# converter_schematic.net
KiCad netlist of a schematic drawn in Altium Designer
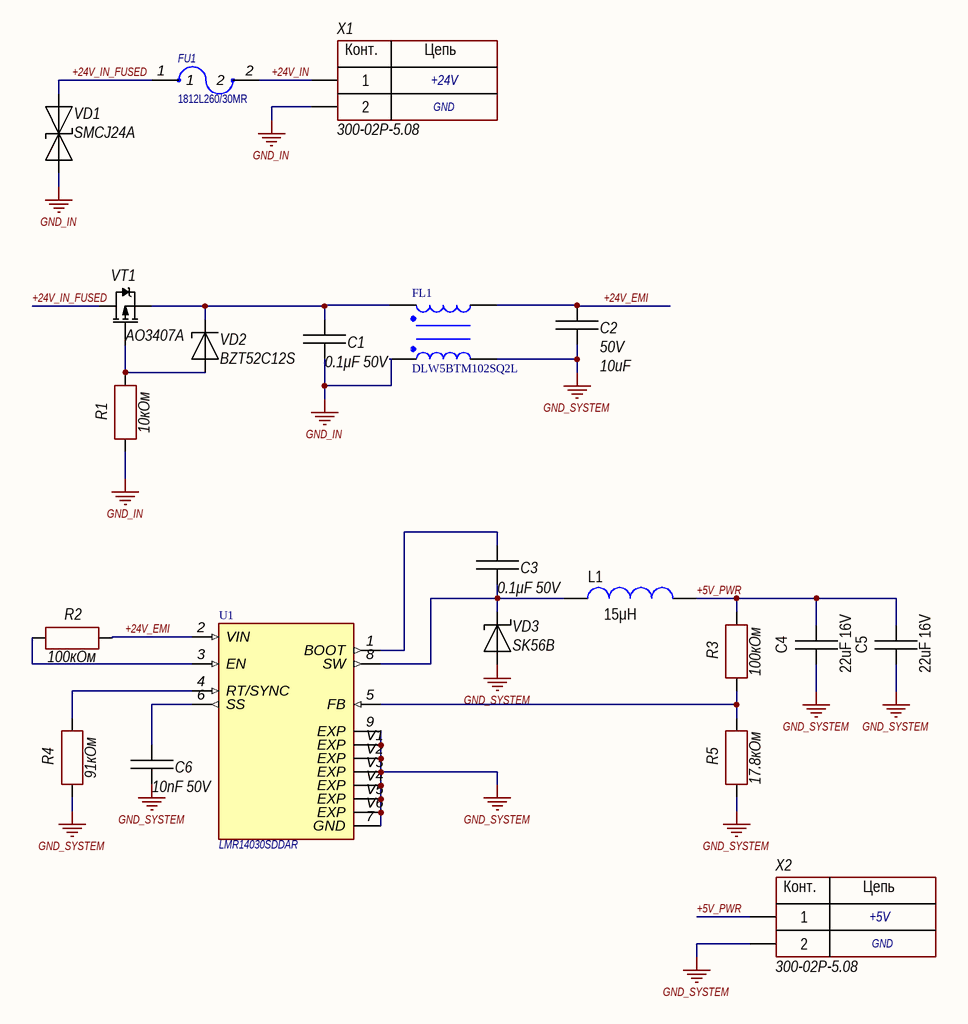
[diagram p0: converter schematic.SchDoc]

(export (version "E")
  (design (tool "Eeschema 10.0.6"))
  (components
    (comp (ref "C1")
      (value "0.1μF 50V")
      (footprint "standard-case:CAP: 0603")
      (fields
        (field (name "MANUFACTURER") "Yageo")
        (field (name "PARTNUMBER") "CC0603KRX7R7BB104")
        (field (name "VALUEMANUFACTURERPARTNUMBER") "Ceramic capacitor, 0.1μF 50V, X7R, ±10%, , 0603, -55...+125°C")
      )
      (libsource (lib "capacitor") (part "Ceramic_0603"))
    )
    (comp (ref "C2")
      (value "10uF")
      (footprint "standard-case:CAP: 1210")
      (fields
        (field (name "MANUFACTURER") "Yageo")
        (field (name "PARTNUMBER") "CC1210KKX7R9BB104")
        (field (name "VALUEMANUFACTURERPARTNUMBER") "Ceramic capacitor, 10uF, X7R, ±10%, 50V, 1210, -55...+125°C")
        (field (name "VOLTAGE") "50V")
      )
      (libsource (lib "capacitor") (part "Ceramic_1210"))
    )
    (comp (ref "C3")
      (value "0.1μF 50V")
      (footprint "standard-case:CAP: 0603")
      (fields
        (field (name "MANUFACTURER") "Yageo")
        (field (name "PARTNUMBER") "CC0603KRX7R7BB104")
        (field (name "VALUEMANUFACTURERPARTNUMBER") "Ceramic capacitor, 0.1μF 50V, X7R, ±10%, , 0603, -55...+125°C")
      )
      (libsource (lib "capacitor") (part "Ceramic_0603"))
    )
    (comp (ref "C4")
      (value "22uF 16V")
      (footprint "standard:CH1206C")
      (libsource (lib "Discrete") (part "Capacitor"))
    )
    (comp (ref "C5")
      (value "22uF 16V")
      (footprint "standard:CH1206C")
      (libsource (lib "Discrete") (part "Capacitor"))
    )
    (comp (ref "C6")
      (value "10nF 50V")
      (footprint "standard-case:CAP: 0603")
      (fields
        (field (name "MANUFACTURER") "Yageo")
        (field (name "PARTNUMBER") "CC0603KRX7R7BB104")
        (field (name "VALUEMANUFACTURERPARTNUMBER") "Ceramic capacitor, 10nF 50V, X7R, ±10%, , 0603, -55...+125°C")
      )
      (libsource (lib "capacitor") (part "Ceramic_0603"))
    )
    (comp (ref "FL1")
      (value "DLW5BTM102SQ2L")
      (footprint "FIL_DLW5BTM102SQ2L")
      (description "2 Line Common Mode Choke Surface Mount 1 kOhms @ 100MHz 2A DCR 34mOhm")
      (fields (field (name "MF") "Murata"))
      (libsource (lib "DLW5BTM102SQ2L") (part "DLW5BTM102SQ2L"))
    )
    (comp (ref "FU1")
      (value "1812L260/30MR")
      (footprint "FUSM4632X200N")
      (description "PTC Resettable Fuse 1.1A(hold) 1.95A(trip) 33VDC 20A 0.8W 0.5s 0.06Ohm SMD Solder Pad 1812 T/R")
      (fields (field (name "MP") "1812L110PRT"))
      (libsource (lib "1812L110PRT") (part "1812L110PRT"))
    )
    (comp (ref "L1")
      (value "~")
      (footprint "custom-case:IND: SRP1265A")
      (fields
        (field (name "MANUFACTURER") "Bourns")
        (field (name "PARTNUMBER") "SRP1265A-4R7M")
        (field (name "VALUEMANUFACTURERPARTNUMBER") "Fixed inductor, , , SRP1265A, 13.5A, -40...+150°C")
        (field (name "SRP1265A-150M") "15μH")
      )
      (libsource (lib "inductor") (part "Inductor_SRP1265A"))
    )
    (comp (ref "R1")
      (value "10кОм")
      (footprint "standard:CH0603R")
      (libsource (lib "Discrete") (part "Resistor"))
    )
    (comp (ref "R2") (value "100кОм") (footprint "standard:CH0603R") (libsource (lib "") (part "Resistor_1")))
    (comp (ref "R3")
      (value "100кОм")
      (footprint "standard:CH0603R")
      (libsource (lib "Discrete") (part "Resistor"))
    )
    (comp (ref "R4")
      (value "91кОм")
      (footprint "standard:CH0603R")
      (libsource (lib "Discrete") (part "Resistor"))
    )
    (comp (ref "R5")
      (value "17.8кОм")
      (footprint "standard:CH0603R")
      (libsource (lib "Discrete") (part "Resistor"))
    )
    (comp (ref "U1")
      (value "LMR14030SDDAR")
      (footprint "SOIC127P600X170-9N")
      (description "SIMPLE SWITCHERÂ® 40-V, 3.5-A, 2.2-MHz step-down converter with 40-uA IQ")
      (fields (field (name "MF") "Texas Instruments"))
      (libsource (lib "LMR14030SDDAR") (part "LMR14030SDDAR"))
    )
    (comp (ref "VD1")
      (value "SMCJ24A")
      (footprint "standard:SMC")
      (libsource (lib "Diods") (part "TVS-diod"))
    )
    (comp (ref "VD2")
      (value "BZT52C12S")
      (footprint "standard:SOD323")
      (libsource (lib "Diods") (part "Diod Zener"))
    )
    (comp (ref "VD3")
      (value "~")
      (footprint "standard-case:DIODE: SMB")
      (fields
        (field (name "MANUFACTURER") "Diodes Incorporated")
        (field (name "VALUEMANUFACTURERPARTNUMBER") "Schottky diode, 80V, 500mA, 1V, 15pF, SOD-123, -55...+150°C")
        (field (name "VOLTAGE") "80V")
        (field (name "PARTNUMBER") "SK56B")
      )
      (libsource (lib "diode") (part "Schottky_single"))
    )
    (comp (ref "VT1")
      (value "AO3407A")
      (footprint "standard:SOT23_132")
      (description "Mosfet")
      (libsource (lib "Transistor") (part "P-chanel"))
    )
    (comp (ref "X1")
      (value "300-02P-5.08")
      (footprint "custom:CON: 300-02P-5.08")
      (libsource (lib "Connectors") (part "2-Connector"))
    )
    (comp (ref "X2")
      (value "300-02P-5.08")
      (footprint "custom:CON: 300-02P-5.08")
      (libsource (lib "Connectors") (part "2-Connector"))
    )
  )
  (nets
    (net (code "1") (name "/+5V_PWR") (class "Default")
      (node (ref "C4") (pin "2") (pinfunction "2_2") (pintype "power_in"))
      (node (ref "C5") (pin "2") (pinfunction "2_2") (pintype "power_in"))
      (node (ref "L1") (pin "1") (pinfunction "1_1") (pintype "passive"))
      (node (ref "R3") (pin "2") (pinfunction "2_2") (pintype "passive"))
      (node (ref "X2") (pin "1") (pinfunction "1_1") (pintype "passive"))
    )
    (net (code "2") (name "/+24V_EMI") (class "Default")
      (node (ref "C2") (pin "2") (pinfunction "2_2") (pintype "passive"))
      (node (ref "FL1") (pin "2") (pinfunction "2_2") (pintype "passive"))
      (node (ref "R2") (pin "2") (pinfunction "2_2") (pintype "passive"))
      (node (ref "U1") (pin "2") (pinfunction "VIN_2") (pintype "input"))
    )
    (net (code "3") (name "/+24V_IN") (class "Default")
      (node (ref "FU1") (pin "2") (pinfunction "2_2") (pintype "passive"))
      (node (ref "X1") (pin "1") (pinfunction "1_1") (pintype "passive"))
    )
    (net (code "4") (name "/+24V_IN_FUSED") (class "Default")
      (node (ref "FU1") (pin "1") (pinfunction "1_1") (pintype "passive"))
      (node (ref "VD1") (pin "1") (pinfunction "A_1") (pintype "passive"))
      (node (ref "VT1") (pin "2") (pinfunction "D_2") (pintype "passive"))
    )
    (net (code "5") (name "GND_IN") (class "Default")
      (node (ref "C1") (pin "1") (pinfunction "1_1") (pintype "passive"))
      (node (ref "FL1") (pin "4") (pinfunction "4_4") (pintype "passive"))
      (node (ref "R1") (pin "1") (pinfunction "1_1") (pintype "passive"))
      (node (ref "VD1") (pin "2") (pinfunction "C_2") (pintype "passive"))
      (node (ref "X1") (pin "2") (pinfunction "2_2") (pintype "passive"))
    )
    (net (code "6") (name "GND_SYSTEM") (class "Default")
      (node (ref "C2") (pin "1") (pinfunction "1_1") (pintype "passive"))
      (node (ref "C4") (pin "1") (pinfunction "1_1") (pintype "power_in"))
      (node (ref "C5") (pin "1") (pinfunction "1_1") (pintype "power_in"))
      (node (ref "C6") (pin "1") (pinfunction "1_1") (pintype "passive"))
      (node (ref "FL1") (pin "3") (pinfunction "3_3") (pintype "passive"))
      (node (ref "R4") (pin "1") (pinfunction "1_1") (pintype "passive"))
      (node (ref "R5") (pin "1") (pinfunction "1_1") (pintype "passive"))
      (node (ref "U1") (pin "7") (pinfunction "GND_7") (pintype "power_in"))
      (node (ref "U1") (pin "9") (pinfunction "EXP_9") (pintype "power_in"))
      (node (ref "U1") (pin "V1") (pinfunction "EXP_V1") (pintype "power_in"))
      (node (ref "U1") (pin "V2") (pinfunction "EXP_V2") (pintype "power_in"))
      (node (ref "U1") (pin "V3") (pinfunction "EXP_V3") (pintype "power_in"))
      (node (ref "U1") (pin "V4") (pinfunction "EXP_V4") (pintype "power_in"))
      (node (ref "U1") (pin "V5") (pinfunction "EXP_V5") (pintype "power_in"))
      (node (ref "U1") (pin "V6") (pinfunction "EXP_V6") (pintype "power_in"))
      (node (ref "VD3") (pin "1") (pinfunction "1_1") (pintype "passive"))
      (node (ref "X2") (pin "2") (pinfunction "2_2") (pintype "passive"))
    )
    (net (code "7") (name "Net-(U1-BOOT)") (class "Default")
      (node (ref "C3") (pin "2") (pinfunction "2_2") (pintype "passive"))
      (node (ref "U1") (pin "1") (pinfunction "BOOT_1") (pintype "output"))
    )
    (net (code "8") (name "Net-(U1-EN)") (class "Default")
      (node (ref "R2") (pin "1") (pinfunction "1_1") (pintype "passive"))
      (node (ref "U1") (pin "3") (pinfunction "EN_3") (pintype "input"))
    )
    (net (code "9") (name "Net-(U1-FB)") (class "Default")
      (node (ref "R3") (pin "1") (pinfunction "1_1") (pintype "passive"))
      (node (ref "R5") (pin "2") (pinfunction "2_2") (pintype "passive"))
      (node (ref "U1") (pin "5") (pinfunction "FB_5") (pintype "input"))
    )
    (net (code "10") (name "Net-(U1-RT{slash}SYNC)") (class "Default")
      (node (ref "R4") (pin "2") (pinfunction "2_2") (pintype "passive"))
      (node (ref "U1") (pin "4") (pinfunction "RT/SYNC_4") (pintype "input"))
    )
    (net (code "11") (name "Net-(U1-SS)") (class "Default")
      (node (ref "C6") (pin "2") (pinfunction "2_2") (pintype "passive"))
      (node (ref "U1") (pin "6") (pinfunction "SS_6") (pintype "output"))
    )
    (net (code "12") (name "Net-(U1-SW)") (class "Default")
      (node (ref "C3") (pin "1") (pinfunction "1_1") (pintype "passive"))
      (node (ref "L1") (pin "2") (pinfunction "2_2") (pintype "passive"))
      (node (ref "U1") (pin "8") (pinfunction "SW_8") (pintype "output"))
      (node (ref "VD3") (pin "2") (pinfunction "2_2") (pintype "passive"))
    )
    (net (code "13") (name "Net-(VD2-A)") (class "Default")
      (node (ref "R1") (pin "2") (pinfunction "2_2") (pintype "passive"))
      (node (ref "VD2") (pin "1") (pinfunction "A_1") (pintype "passive"))
      (node (ref "VT1") (pin "1") (pinfunction "G_1") (pintype "passive"))
    )
    (net (code "14") (name "Net-(VD2-C)") (class "Default")
      (node (ref "C1") (pin "2") (pinfunction "2_2") (pintype "passive"))
      (node (ref "FL1") (pin "1") (pinfunction "1_1") (pintype "passive"))
      (node (ref "VD2") (pin "2") (pinfunction "C_2") (pintype "passive"))
      (node (ref "VT1") (pin "3") (pinfunction "S_3") (pintype "passive"))
    )
  )
)
